# optopara_rroE3.net
KiCad netlist of a schematic drawn in Altium Designer
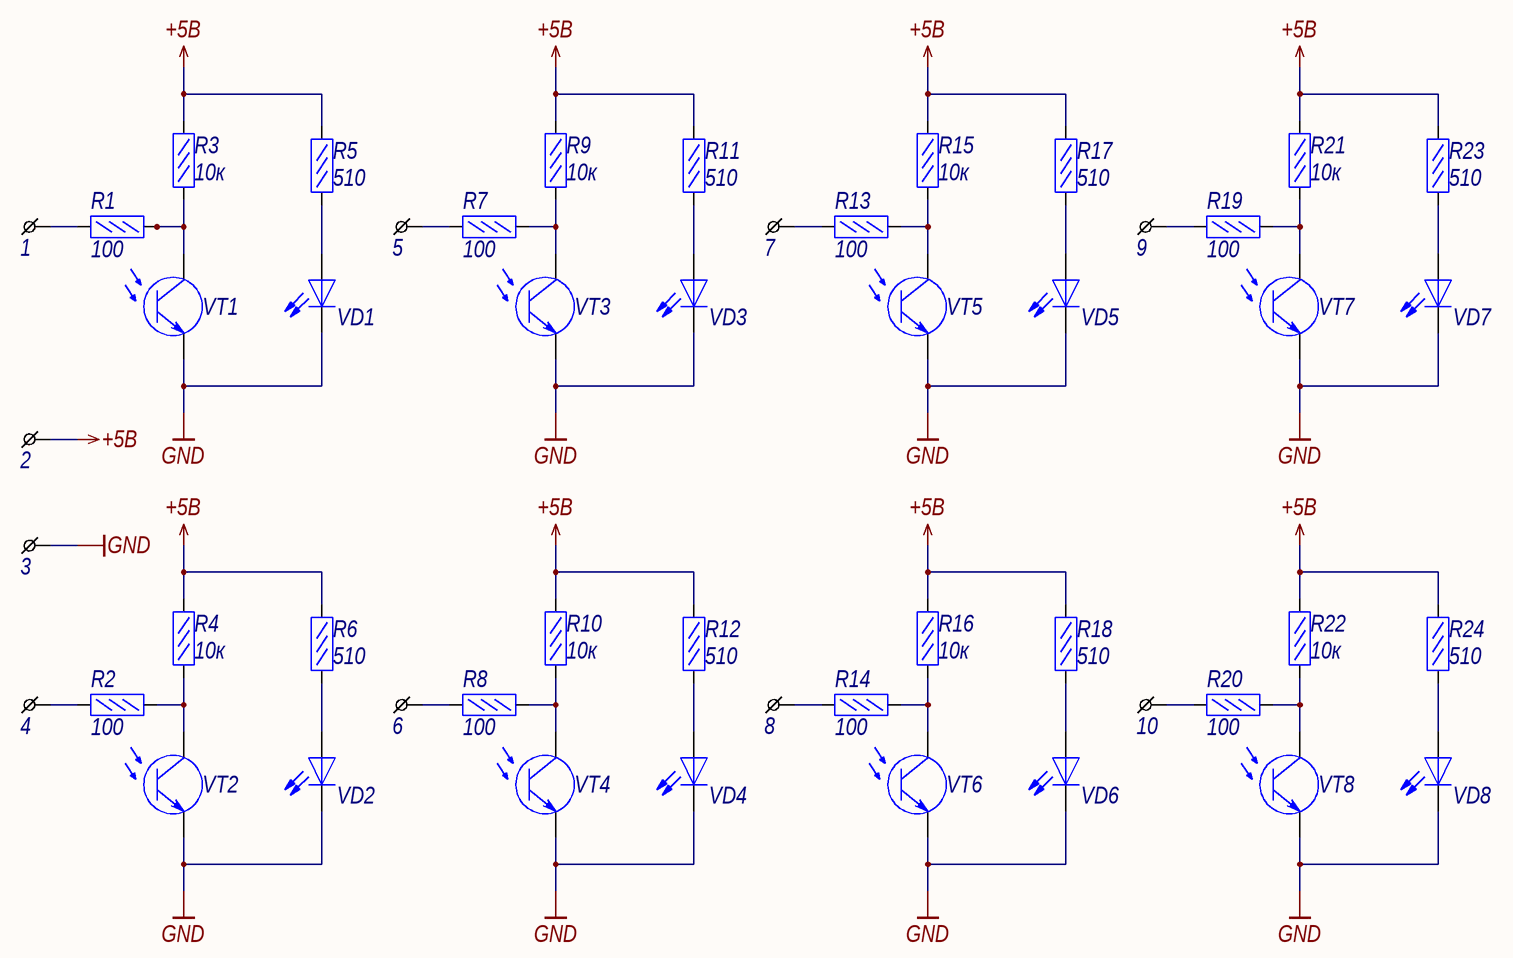
[diagram p0: optopara_rroE3.SchDoc]

(export (version "E")
  (design (tool "Eeschema 10.0.6"))
  (components
    (comp (ref "1") (value "MNT_HOLE") (footprint "TP_1X1") (libsource (lib "mount_parts") (part "MNT_HOLE")))
    (comp (ref "2") (value "MNT_HOLE") (footprint "TP_1X1") (libsource (lib "mount_parts") (part "MNT_HOLE")))
    (comp (ref "3") (value "MNT_HOLE") (footprint "TP_1X1") (libsource (lib "mount_parts") (part "MNT_HOLE")))
    (comp (ref "4") (value "MNT_HOLE") (footprint "TP_1X1") (libsource (lib "mount_parts") (part "MNT_HOLE")))
    (comp (ref "5") (value "MNT_HOLE") (footprint "TP_1X1") (libsource (lib "mount_parts") (part "MNT_HOLE")))
    (comp (ref "6") (value "MNT_HOLE") (footprint "TP_1X1") (libsource (lib "mount_parts") (part "MNT_HOLE")))
    (comp (ref "7") (value "MNT_HOLE") (footprint "TP_1X1") (libsource (lib "mount_parts") (part "MNT_HOLE")))
    (comp (ref "8") (value "MNT_HOLE") (footprint "TP_1X1") (libsource (lib "mount_parts") (part "MNT_HOLE")))
    (comp (ref "9") (value "MNT_HOLE") (footprint "TP_1X1") (libsource (lib "mount_parts") (part "MNT_HOLE")))
    (comp (ref "10")
      (value "MNT_HOLE")
      (footprint "TP_1X1")
      (libsource (lib "mount_parts") (part "MNT_HOLE"))
    )
    (comp (ref "R1")
      (value "100")
      (footprint "R0603")
      (description "Резистор 100 Ом 0,1Вт 1%")
      (fields (field (name "MANUFACTURER") "YAGEO") (field (name "TOLERANCE") "1%"))
      (libsource (lib "resistors") (part "RC0603FR-07100RL"))
    )
    (comp (ref "R2")
      (value "100")
      (footprint "R0603")
      (description "Резистор 100 Ом 0,1Вт 1%")
      (fields (field (name "MANUFACTURER") "YAGEO") (field (name "TOLERANCE") "1%"))
      (libsource (lib "resistors") (part "RC0603FR-07100RL"))
    )
    (comp (ref "R3")
      (value "10к")
      (footprint "R0603")
      (description "Резистор 10кОм 0,063Вт 1%")
      (fields (field (name "MANUFACTURER") "YAGEO") (field (name "TOLERANCE") "1%"))
      (libsource (lib "resistors") (part "RC0603FR-0710KL"))
    )
    (comp (ref "R4")
      (value "10к")
      (footprint "R0603")
      (description "Резистор 10кОм 0,063Вт 1%")
      (fields (field (name "MANUFACTURER") "YAGEO") (field (name "TOLERANCE") "1%"))
      (libsource (lib "resistors") (part "RC0603FR-0710KL"))
    )
    (comp (ref "R5")
      (value "510")
      (footprint "R0603")
      (description "Резистор 510 Ом 0,1Вт 1%")
      (fields (field (name "MANUFACTURER") "YAGEO") (field (name "TOLERANCE") "1%"))
      (libsource (lib "resistors") (part "RC0603FR-07510RL"))
    )
    (comp (ref "R6")
      (value "510")
      (footprint "R0603")
      (description "Резистор 510 Ом 0,1Вт 1%")
      (fields (field (name "MANUFACTURER") "YAGEO") (field (name "TOLERANCE") "1%"))
      (libsource (lib "resistors") (part "RC0603FR-07510RL"))
    )
    (comp (ref "R7")
      (value "100")
      (footprint "R0603")
      (description "Резистор 100 Ом 0,1Вт 1%")
      (fields (field (name "MANUFACTURER") "YAGEO") (field (name "TOLERANCE") "1%"))
      (libsource (lib "resistors") (part "RC0603FR-07100RL"))
    )
    (comp (ref "R8")
      (value "100")
      (footprint "R0603")
      (description "Резистор 100 Ом 0,1Вт 1%")
      (fields (field (name "MANUFACTURER") "YAGEO") (field (name "TOLERANCE") "1%"))
      (libsource (lib "resistors") (part "RC0603FR-07100RL"))
    )
    (comp (ref "R9")
      (value "10к")
      (footprint "R0603")
      (description "Резистор 10кОм 0,063Вт 1%")
      (fields (field (name "MANUFACTURER") "YAGEO") (field (name "TOLERANCE") "1%"))
      (libsource (lib "resistors") (part "RC0603FR-0710KL"))
    )
    (comp (ref "R10")
      (value "10к")
      (footprint "R0603")
      (description "Резистор 10кОм 0,063Вт 1%")
      (fields (field (name "MANUFACTURER") "YAGEO") (field (name "TOLERANCE") "1%"))
      (libsource (lib "resistors") (part "RC0603FR-0710KL"))
    )
    (comp (ref "R11")
      (value "510")
      (footprint "R0603")
      (description "Резистор 510 Ом 0,1Вт 1%")
      (fields (field (name "MANUFACTURER") "YAGEO") (field (name "TOLERANCE") "1%"))
      (libsource (lib "resistors") (part "RC0603FR-07510RL"))
    )
    (comp (ref "R12")
      (value "510")
      (footprint "R0603")
      (description "Резистор 510 Ом 0,1Вт 1%")
      (fields (field (name "MANUFACTURER") "YAGEO") (field (name "TOLERANCE") "1%"))
      (libsource (lib "resistors") (part "RC0603FR-07510RL"))
    )
    (comp (ref "R13")
      (value "100")
      (footprint "R0603")
      (description "Резистор 100 Ом 0,1Вт 1%")
      (fields (field (name "MANUFACTURER") "YAGEO") (field (name "TOLERANCE") "1%"))
      (libsource (lib "resistors") (part "RC0603FR-07100RL"))
    )
    (comp (ref "R14")
      (value "100")
      (footprint "R0603")
      (description "Резистор 100 Ом 0,1Вт 1%")
      (fields (field (name "MANUFACTURER") "YAGEO") (field (name "TOLERANCE") "1%"))
      (libsource (lib "resistors") (part "RC0603FR-07100RL"))
    )
    (comp (ref "R15")
      (value "10к")
      (footprint "R0603")
      (description "Резистор 10кОм 0,063Вт 1%")
      (fields (field (name "MANUFACTURER") "YAGEO") (field (name "TOLERANCE") "1%"))
      (libsource (lib "resistors") (part "RC0603FR-0710KL"))
    )
    (comp (ref "R16")
      (value "10к")
      (footprint "R0603")
      (description "Резистор 10кОм 0,063Вт 1%")
      (fields (field (name "MANUFACTURER") "YAGEO") (field (name "TOLERANCE") "1%"))
      (libsource (lib "resistors") (part "RC0603FR-0710KL"))
    )
    (comp (ref "R17")
      (value "510")
      (footprint "R0603")
      (description "Резистор 510 Ом 0,1Вт 1%")
      (fields (field (name "MANUFACTURER") "YAGEO") (field (name "TOLERANCE") "1%"))
      (libsource (lib "resistors") (part "RC0603FR-07510RL"))
    )
    (comp (ref "R18")
      (value "510")
      (footprint "R0603")
      (description "Резистор 510 Ом 0,1Вт 1%")
      (fields (field (name "MANUFACTURER") "YAGEO") (field (name "TOLERANCE") "1%"))
      (libsource (lib "resistors") (part "RC0603FR-07510RL"))
    )
    (comp (ref "R19")
      (value "100")
      (footprint "R0603")
      (description "Резистор 100 Ом 0,1Вт 1%")
      (fields (field (name "MANUFACTURER") "YAGEO") (field (name "TOLERANCE") "1%"))
      (libsource (lib "resistors") (part "RC0603FR-07100RL"))
    )
    (comp (ref "R20")
      (value "100")
      (footprint "R0603")
      (description "Резистор 100 Ом 0,1Вт 1%")
      (fields (field (name "MANUFACTURER") "YAGEO") (field (name "TOLERANCE") "1%"))
      (libsource (lib "resistors") (part "RC0603FR-07100RL"))
    )
    (comp (ref "R21")
      (value "10к")
      (footprint "R0603")
      (description "Резистор 10кОм 0,063Вт 1%")
      (fields (field (name "MANUFACTURER") "YAGEO") (field (name "TOLERANCE") "1%"))
      (libsource (lib "resistors") (part "RC0603FR-0710KL"))
    )
    (comp (ref "R22")
      (value "10к")
      (footprint "R0603")
      (description "Резистор 10кОм 0,063Вт 1%")
      (fields (field (name "MANUFACTURER") "YAGEO") (field (name "TOLERANCE") "1%"))
      (libsource (lib "resistors") (part "RC0603FR-0710KL"))
    )
    (comp (ref "R23")
      (value "510")
      (footprint "R0603")
      (description "Резистор 510 Ом 0,1Вт 1%")
      (fields (field (name "MANUFACTURER") "YAGEO") (field (name "TOLERANCE") "1%"))
      (libsource (lib "resistors") (part "RC0603FR-07510RL"))
    )
    (comp (ref "R24")
      (value "510")
      (footprint "R0603")
      (description "Резистор 510 Ом 0,1Вт 1%")
      (fields (field (name "MANUFACTURER") "YAGEO") (field (name "TOLERANCE") "1%"))
      (libsource (lib "resistors") (part "RC0603FR-07510RL"))
    )
    (comp (ref "VD1")
      (value "~")
      (footprint "LED_5mm")
      (description "ИК светодиод")
      (libsource (lib "diodes") (part "IR_LED"))
    )
    (comp (ref "VD2")
      (value "~")
      (footprint "LED_5mm")
      (description "ИК светодиод")
      (libsource (lib "diodes") (part "IR_LED"))
    )
    (comp (ref "VD3")
      (value "~")
      (footprint "LED_5mm")
      (description "ИК светодиод")
      (libsource (lib "diodes") (part "IR_LED"))
    )
    (comp (ref "VD4")
      (value "~")
      (footprint "LED_5mm")
      (description "ИК светодиод")
      (libsource (lib "diodes") (part "IR_LED"))
    )
    (comp (ref "VD5")
      (value "~")
      (footprint "LED_5mm")
      (description "ИК светодиод")
      (libsource (lib "diodes") (part "IR_LED"))
    )
    (comp (ref "VD6")
      (value "~")
      (footprint "LED_5mm")
      (description "ИК светодиод")
      (libsource (lib "diodes") (part "IR_LED"))
    )
    (comp (ref "VD7")
      (value "~")
      (footprint "LED_5mm")
      (description "ИК светодиод")
      (libsource (lib "diodes") (part "IR_LED"))
    )
    (comp (ref "VD8")
      (value "~")
      (footprint "LED_5mm")
      (description "ИК светодиод")
      (libsource (lib "diodes") (part "IR_LED"))
    )
    (comp (ref "VT1")
      (value "-")
      (footprint "LED_5mm")
      (description "Биполярный NPN транзистор")
      (libsource (lib "transistors") (part "BJTfoto"))
    )
    (comp (ref "VT2")
      (value "-")
      (footprint "LED_5mm")
      (description "Биполярный NPN транзистор")
      (libsource (lib "transistors") (part "BJTfoto"))
    )
    (comp (ref "VT3")
      (value "-")
      (footprint "LED_5mm")
      (description "Биполярный NPN транзистор")
      (libsource (lib "transistors") (part "BJTfoto"))
    )
    (comp (ref "VT4")
      (value "-")
      (footprint "LED_5mm")
      (description "Биполярный NPN транзистор")
      (libsource (lib "transistors") (part "BJTfoto"))
    )
    (comp (ref "VT5")
      (value "-")
      (footprint "LED_5mm")
      (description "Биполярный NPN транзистор")
      (libsource (lib "transistors") (part "BJTfoto"))
    )
    (comp (ref "VT6")
      (value "-")
      (footprint "LED_5mm")
      (description "Биполярный NPN транзистор")
      (libsource (lib "transistors") (part "BJTfoto"))
    )
    (comp (ref "VT7")
      (value "-")
      (footprint "LED_5mm")
      (description "Биполярный NPN транзистор")
      (libsource (lib "transistors") (part "BJTfoto"))
    )
    (comp (ref "VT8")
      (value "-")
      (footprint "LED_5mm")
      (description "Биполярный NPN транзистор")
      (libsource (lib "transistors") (part "BJTfoto"))
    )
  )
  (nets
    (net (code "1") (name "+5В") (class "Default")
      (node (ref "2") (pin "1") (pinfunction "1_1") (pintype "passive"))
      (node (ref "R10") (pin "2") (pinfunction "2_2") (pintype "passive"))
      (node (ref "R11") (pin "2") (pinfunction "2_2") (pintype "passive"))
      (node (ref "R12") (pin "2") (pinfunction "2_2") (pintype "passive"))
      (node (ref "R15") (pin "2") (pinfunction "2_2") (pintype "passive"))
      (node (ref "R16") (pin "2") (pinfunction "2_2") (pintype "passive"))
      (node (ref "R17") (pin "2") (pinfunction "2_2") (pintype "passive"))
      (node (ref "R18") (pin "2") (pinfunction "2_2") (pintype "passive"))
      (node (ref "R21") (pin "2") (pinfunction "2_2") (pintype "passive"))
      (node (ref "R22") (pin "2") (pinfunction "2_2") (pintype "passive"))
      (node (ref "R23") (pin "2") (pinfunction "2_2") (pintype "passive"))
      (node (ref "R24") (pin "2") (pinfunction "2_2") (pintype "passive"))
      (node (ref "R3") (pin "2") (pinfunction "2_2") (pintype "passive"))
      (node (ref "R4") (pin "2") (pinfunction "2_2") (pintype "passive"))
      (node (ref "R5") (pin "2") (pinfunction "2_2") (pintype "passive"))
      (node (ref "R6") (pin "2") (pinfunction "2_2") (pintype "passive"))
      (node (ref "R9") (pin "2") (pinfunction "2_2") (pintype "passive"))
    )
    (net (code "2") (name "GND") (class "Default")
      (node (ref "3") (pin "1") (pinfunction "1_1") (pintype "passive"))
      (node (ref "VD1") (pin "2") (pinfunction "K_2") (pintype "passive"))
      (node (ref "VD2") (pin "2") (pinfunction "K_2") (pintype "passive"))
      (node (ref "VD3") (pin "2") (pinfunction "K_2") (pintype "passive"))
      (node (ref "VD4") (pin "2") (pinfunction "K_2") (pintype "passive"))
      (node (ref "VD5") (pin "2") (pinfunction "K_2") (pintype "passive"))
      (node (ref "VD6") (pin "2") (pinfunction "K_2") (pintype "passive"))
      (node (ref "VD7") (pin "2") (pinfunction "K_2") (pintype "passive"))
      (node (ref "VD8") (pin "2") (pinfunction "K_2") (pintype "passive"))
      (node (ref "VT1") (pin "2") (pintype "passive"))
      (node (ref "VT2") (pin "2") (pintype "passive"))
      (node (ref "VT3") (pin "2") (pintype "passive"))
      (node (ref "VT4") (pin "2") (pintype "passive"))
      (node (ref "VT5") (pin "2") (pintype "passive"))
      (node (ref "VT6") (pin "2") (pintype "passive"))
      (node (ref "VT7") (pin "2") (pintype "passive"))
      (node (ref "VT8") (pin "2") (pintype "passive"))
    )
    (net (code "3") (name "Net-(1-Pad1)") (class "Default")
      (node (ref "1") (pin "1") (pinfunction "1_1") (pintype "passive"))
      (node (ref "R1") (pin "1") (pinfunction "1_1") (pintype "passive"))
    )
    (net (code "4") (name "Net-(4-Pad1)") (class "Default")
      (node (ref "4") (pin "1") (pinfunction "1_1") (pintype "passive"))
      (node (ref "R2") (pin "1") (pinfunction "1_1") (pintype "passive"))
    )
    (net (code "5") (name "Net-(5-Pad1)") (class "Default")
      (node (ref "5") (pin "1") (pinfunction "1_1") (pintype "passive"))
      (node (ref "R7") (pin "1") (pinfunction "1_1") (pintype "passive"))
    )
    (net (code "6") (name "Net-(6-Pad1)") (class "Default")
      (node (ref "6") (pin "1") (pinfunction "1_1") (pintype "passive"))
      (node (ref "R8") (pin "1") (pinfunction "1_1") (pintype "passive"))
    )
    (net (code "7") (name "Net-(7-Pad1)") (class "Default")
      (node (ref "7") (pin "1") (pinfunction "1_1") (pintype "passive"))
      (node (ref "R13") (pin "1") (pinfunction "1_1") (pintype "passive"))
    )
    (net (code "8") (name "Net-(8-Pad1)") (class "Default")
      (node (ref "8") (pin "1") (pinfunction "1_1") (pintype "passive"))
      (node (ref "R14") (pin "1") (pinfunction "1_1") (pintype "passive"))
    )
    (net (code "9") (name "Net-(9-Pad1)") (class "Default")
      (node (ref "9") (pin "1") (pinfunction "1_1") (pintype "passive"))
      (node (ref "R19") (pin "1") (pinfunction "1_1") (pintype "passive"))
    )
    (net (code "10") (name "Net-(10-Pad1)") (class "Default")
      (node (ref "10") (pin "1") (pinfunction "1_1") (pintype "passive"))
      (node (ref "R20") (pin "1") (pinfunction "1_1") (pintype "passive"))
    )
    (net (code "11") (name "Net-(R1-Pad2)") (class "Default")
      (node (ref "R1") (pin "2") (pinfunction "2_2") (pintype "passive"))
      (node (ref "R3") (pin "1") (pinfunction "1_1") (pintype "passive"))
      (node (ref "VT1") (pin "1") (pintype "passive"))
    )
    (net (code "12") (name "Net-(R2-Pad2)") (class "Default")
      (node (ref "R2") (pin "2") (pinfunction "2_2") (pintype "passive"))
      (node (ref "R4") (pin "1") (pinfunction "1_1") (pintype "passive"))
      (node (ref "VT2") (pin "1") (pintype "passive"))
    )
    (net (code "13") (name "Net-(R7-Pad2)") (class "Default")
      (node (ref "R7") (pin "2") (pinfunction "2_2") (pintype "passive"))
      (node (ref "R9") (pin "1") (pinfunction "1_1") (pintype "passive"))
      (node (ref "VT3") (pin "1") (pintype "passive"))
    )
    (net (code "14") (name "Net-(R10-Pad1)") (class "Default")
      (node (ref "R10") (pin "1") (pinfunction "1_1") (pintype "passive"))
      (node (ref "R8") (pin "2") (pinfunction "2_2") (pintype "passive"))
      (node (ref "VT4") (pin "1") (pintype "passive"))
    )
    (net (code "15") (name "Net-(R13-Pad2)") (class "Default")
      (node (ref "R13") (pin "2") (pinfunction "2_2") (pintype "passive"))
      (node (ref "R15") (pin "1") (pinfunction "1_1") (pintype "passive"))
      (node (ref "VT5") (pin "1") (pintype "passive"))
    )
    (net (code "16") (name "Net-(R14-Pad2)") (class "Default")
      (node (ref "R14") (pin "2") (pinfunction "2_2") (pintype "passive"))
      (node (ref "R16") (pin "1") (pinfunction "1_1") (pintype "passive"))
      (node (ref "VT6") (pin "1") (pintype "passive"))
    )
    (net (code "17") (name "Net-(R19-Pad2)") (class "Default")
      (node (ref "R19") (pin "2") (pinfunction "2_2") (pintype "passive"))
      (node (ref "R21") (pin "1") (pinfunction "1_1") (pintype "passive"))
      (node (ref "VT7") (pin "1") (pintype "passive"))
    )
    (net (code "18") (name "Net-(R20-Pad2)") (class "Default")
      (node (ref "R20") (pin "2") (pinfunction "2_2") (pintype "passive"))
      (node (ref "R22") (pin "1") (pinfunction "1_1") (pintype "passive"))
      (node (ref "VT8") (pin "1") (pintype "passive"))
    )
    (net (code "19") (name "Net-(VD1-A)") (class "Default")
      (node (ref "R5") (pin "1") (pinfunction "1_1") (pintype "passive"))
      (node (ref "VD1") (pin "1") (pinfunction "A_1") (pintype "passive"))
    )
    (net (code "20") (name "Net-(VD2-A)") (class "Default")
      (node (ref "R6") (pin "1") (pinfunction "1_1") (pintype "passive"))
      (node (ref "VD2") (pin "1") (pinfunction "A_1") (pintype "passive"))
    )
    (net (code "21") (name "Net-(VD3-A)") (class "Default")
      (node (ref "R11") (pin "1") (pinfunction "1_1") (pintype "passive"))
      (node (ref "VD3") (pin "1") (pinfunction "A_1") (pintype "passive"))
    )
    (net (code "22") (name "Net-(VD4-A)") (class "Default")
      (node (ref "R12") (pin "1") (pinfunction "1_1") (pintype "passive"))
      (node (ref "VD4") (pin "1") (pinfunction "A_1") (pintype "passive"))
    )
    (net (code "23") (name "Net-(VD5-A)") (class "Default")
      (node (ref "R17") (pin "1") (pinfunction "1_1") (pintype "passive"))
      (node (ref "VD5") (pin "1") (pinfunction "A_1") (pintype "passive"))
    )
    (net (code "24") (name "Net-(VD6-A)") (class "Default")
      (node (ref "R18") (pin "1") (pinfunction "1_1") (pintype "passive"))
      (node (ref "VD6") (pin "1") (pinfunction "A_1") (pintype "passive"))
    )
    (net (code "25") (name "Net-(VD7-A)") (class "Default")
      (node (ref "R23") (pin "1") (pinfunction "1_1") (pintype "passive"))
      (node (ref "VD7") (pin "1") (pinfunction "A_1") (pintype "passive"))
    )
    (net (code "26") (name "Net-(VD8-A)") (class "Default")
      (node (ref "R24") (pin "1") (pinfunction "1_1") (pintype "passive"))
      (node (ref "VD8") (pin "1") (pinfunction "A_1") (pintype "passive"))
    )
  )
)
